# DDR3_SODIMM_SPD_Breakout.net
KiCad netlist of a schematic drawn in Altium Designer
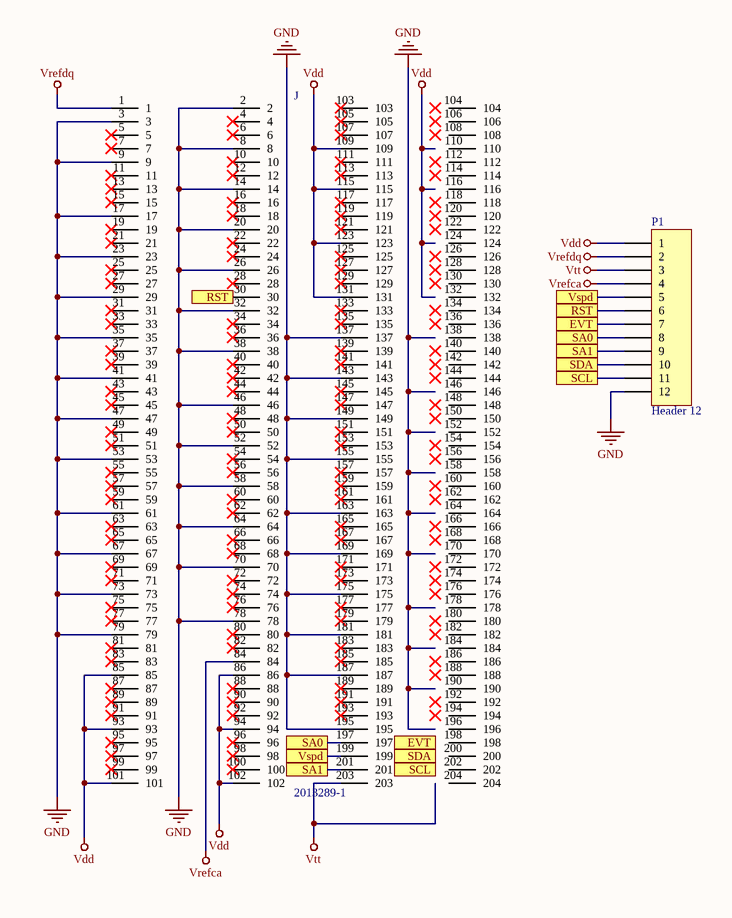
[diagram p0: DDR3 SODIMM SPD Breakout.SchDoc]

(export (version "E")
  (design (tool "Eeschema 10.0.6"))
  (components
    (comp (ref "J")
      (value "2013289-1")
      (footprint "2020-09-26_17-27-19:TE_2013289-1")
      (description "204 Position 0.6 mm Pitch Right Angle Surface Mount Socket DIMM Connector")
      (fields (field (name "DIGI-KEY_PART_NUMBER") "A115021-ND") (field (name "MF") "TE Connectivity"))
      (libsource (lib "2020-09-26_17-27-19") (part "2013289-1"))
    )
    (comp (ref "P1")
      (value "Header 12")
      (footprint "HDR1X12")
      (description "Header, 12-Pin")
      (fields (field (name "PUBLISHER") "Altium Limited"))
      (libsource (lib "Miscellaneous Connectors") (part "Header 12"))
    )
  )
  (nets
    (net (code "1") (name "/EVT") (class "Default")
      (node (ref "P1") (pin "7") (pinfunction "7_7") (pintype "passive"))
    )
    (net (code "2") (name "/RST") (class "Default")
      (node (ref "J") (pin "30") (pinfunction "30_30") (pintype "passive"))
      (node (ref "P1") (pin "6") (pinfunction "6_6") (pintype "passive"))
    )
    (net (code "3") (name "/SA0") (class "Default")
      (node (ref "J") (pin "197") (pinfunction "197_197") (pintype "passive"))
      (node (ref "P1") (pin "8") (pinfunction "8_8") (pintype "passive"))
    )
    (net (code "4") (name "/SA1") (class "Default")
      (node (ref "J") (pin "201") (pinfunction "201_201") (pintype "passive"))
      (node (ref "P1") (pin "9") (pinfunction "9_9") (pintype "passive"))
    )
    (net (code "5") (name "/SCL") (class "Default")
      (node (ref "P1") (pin "11") (pinfunction "11_11") (pintype "passive"))
    )
    (net (code "6") (name "/SDA") (class "Default")
      (node (ref "P1") (pin "10") (pinfunction "10_10") (pintype "passive"))
    )
    (net (code "7") (name "/Vspd") (class "Default")
      (node (ref "J") (pin "199") (pinfunction "199_199") (pintype "passive"))
      (node (ref "P1") (pin "5") (pinfunction "5_5") (pintype "passive"))
    )
    (net (code "8") (name "GND") (class "Default")
      (node (ref "J") (pin "137") (pinfunction "137_137") (pintype "passive"))
      (node (ref "J") (pin "14") (pinfunction "14_14") (pintype "passive"))
      (node (ref "J") (pin "143") (pinfunction "143_143") (pintype "passive"))
      (node (ref "J") (pin "149") (pinfunction "149_149") (pintype "passive"))
      (node (ref "J") (pin "155") (pinfunction "155_155") (pintype "passive"))
      (node (ref "J") (pin "163") (pinfunction "163_163") (pintype "passive"))
      (node (ref "J") (pin "169") (pinfunction "169_169") (pintype "passive"))
      (node (ref "J") (pin "17") (pinfunction "17_17") (pintype "passive"))
      (node (ref "J") (pin "175") (pinfunction "175_175") (pintype "passive"))
      (node (ref "J") (pin "181") (pinfunction "181_181") (pintype "passive"))
      (node (ref "J") (pin "187") (pinfunction "187_187") (pintype "passive"))
      (node (ref "J") (pin "195") (pinfunction "195_195") (pintype "passive"))
      (node (ref "J") (pin "2") (pinfunction "2_2") (pintype "passive"))
      (node (ref "J") (pin "20") (pinfunction "20_20") (pintype "passive"))
      (node (ref "J") (pin "23") (pinfunction "23_23") (pintype "passive"))
      (node (ref "J") (pin "26") (pinfunction "26_26") (pintype "passive"))
      (node (ref "J") (pin "29") (pinfunction "29_29") (pintype "passive"))
      (node (ref "J") (pin "3") (pinfunction "3_3") (pintype "passive"))
      (node (ref "J") (pin "32") (pinfunction "32_32") (pintype "passive"))
      (node (ref "J") (pin "35") (pinfunction "35_35") (pintype "passive"))
      (node (ref "J") (pin "38") (pinfunction "38_38") (pintype "passive"))
      (node (ref "J") (pin "41") (pinfunction "41_41") (pintype "passive"))
      (node (ref "J") (pin "46") (pinfunction "46_46") (pintype "passive"))
      (node (ref "J") (pin "47") (pinfunction "47_47") (pintype "passive"))
      (node (ref "J") (pin "52") (pinfunction "52_52") (pintype "passive"))
      (node (ref "J") (pin "53") (pinfunction "53_53") (pintype "passive"))
      (node (ref "J") (pin "58") (pinfunction "58_58") (pintype "passive"))
      (node (ref "J") (pin "61") (pinfunction "61_61") (pintype "passive"))
      (node (ref "J") (pin "64") (pinfunction "64_64") (pintype "passive"))
      (node (ref "J") (pin "67") (pinfunction "67_67") (pintype "passive"))
      (node (ref "J") (pin "70") (pinfunction "70_70") (pintype "passive"))
      (node (ref "J") (pin "73") (pinfunction "73_73") (pintype "passive"))
      (node (ref "J") (pin "78") (pinfunction "78_78") (pintype "passive"))
      (node (ref "J") (pin "79") (pinfunction "79_79") (pintype "passive"))
      (node (ref "J") (pin "8") (pinfunction "8_8") (pintype "passive"))
      (node (ref "J") (pin "9") (pinfunction "9_9") (pintype "passive"))
      (node (ref "P1") (pin "12") (pinfunction "12_12") (pintype "passive"))
    )
    (net (code "9") (name "Vdd") (class "Default")
      (node (ref "J") (pin "101") (pinfunction "101_101") (pintype "passive"))
      (node (ref "J") (pin "102") (pinfunction "102_102") (pintype "passive"))
      (node (ref "J") (pin "109") (pinfunction "109_109") (pintype "passive"))
      (node (ref "J") (pin "115") (pinfunction "115_115") (pintype "passive"))
      (node (ref "J") (pin "123") (pinfunction "123_123") (pintype "passive"))
      (node (ref "J") (pin "131") (pinfunction "131_131") (pintype "passive"))
      (node (ref "J") (pin "85") (pinfunction "85_85") (pintype "passive"))
      (node (ref "J") (pin "86") (pinfunction "86_86") (pintype "passive"))
      (node (ref "J") (pin "93") (pinfunction "93_93") (pintype "passive"))
      (node (ref "J") (pin "94") (pinfunction "94_94") (pintype "passive"))
      (node (ref "P1") (pin "1") (pinfunction "1_1") (pintype "passive"))
    )
    (net (code "10") (name "Vrefca") (class "Default")
      (node (ref "J") (pin "84") (pinfunction "84_84") (pintype "passive"))
      (node (ref "P1") (pin "4") (pinfunction "4_4") (pintype "passive"))
    )
    (net (code "11") (name "Vrefdq") (class "Default")
      (node (ref "J") (pin "1") (pinfunction "1_1") (pintype "passive"))
      (node (ref "P1") (pin "2") (pinfunction "2_2") (pintype "passive"))
    )
    (net (code "12") (name "Vtt") (class "Default")
      (node (ref "J") (pin "203") (pinfunction "203_203") (pintype "passive"))
      (node (ref "P1") (pin "3") (pinfunction "3_3") (pintype "passive"))
    )
    (net (code "13") (name "unconnected-(J-Pad4)") (class "Default")
      (node (ref "J") (pin "4") (pinfunction "4_4") (pintype "passive+no_connect"))
    )
    (net (code "14") (name "unconnected-(J-Pad5)") (class "Default")
      (node (ref "J") (pin "5") (pinfunction "5_5") (pintype "passive+no_connect"))
    )
    (net (code "15") (name "unconnected-(J-Pad6)") (class "Default")
      (node (ref "J") (pin "6") (pinfunction "6_6") (pintype "passive+no_connect"))
    )
    (net (code "16") (name "unconnected-(J-Pad7)") (class "Default")
      (node (ref "J") (pin "7") (pinfunction "7_7") (pintype "passive+no_connect"))
    )
    (net (code "17") (name "unconnected-(J-Pad10)") (class "Default")
      (node (ref "J") (pin "10") (pinfunction "10_10") (pintype "passive+no_connect"))
    )
    (net (code "18") (name "unconnected-(J-Pad11)") (class "Default")
      (node (ref "J") (pin "11") (pinfunction "11_11") (pintype "passive+no_connect"))
    )
    (net (code "19") (name "unconnected-(J-Pad12)") (class "Default")
      (node (ref "J") (pin "12") (pinfunction "12_12") (pintype "passive+no_connect"))
    )
    (net (code "20") (name "unconnected-(J-Pad13)") (class "Default")
      (node (ref "J") (pin "13") (pinfunction "13_13") (pintype "passive+no_connect"))
    )
    (net (code "21") (name "unconnected-(J-Pad15)") (class "Default")
      (node (ref "J") (pin "15") (pinfunction "15_15") (pintype "passive+no_connect"))
    )
    (net (code "22") (name "unconnected-(J-Pad16)") (class "Default")
      (node (ref "J") (pin "16") (pinfunction "16_16") (pintype "passive+no_connect"))
    )
    (net (code "23") (name "unconnected-(J-Pad18)") (class "Default")
      (node (ref "J") (pin "18") (pinfunction "18_18") (pintype "passive+no_connect"))
    )
    (net (code "24") (name "unconnected-(J-Pad19)") (class "Default")
      (node (ref "J") (pin "19") (pinfunction "19_19") (pintype "passive+no_connect"))
    )
    (net (code "25") (name "unconnected-(J-Pad21)") (class "Default")
      (node (ref "J") (pin "21") (pinfunction "21_21") (pintype "passive+no_connect"))
    )
    (net (code "26") (name "unconnected-(J-Pad22)") (class "Default")
      (node (ref "J") (pin "22") (pinfunction "22_22") (pintype "passive+no_connect"))
    )
    (net (code "27") (name "unconnected-(J-Pad24)") (class "Default")
      (node (ref "J") (pin "24") (pinfunction "24_24") (pintype "passive+no_connect"))
    )
    (net (code "28") (name "unconnected-(J-Pad25)") (class "Default")
      (node (ref "J") (pin "25") (pinfunction "25_25") (pintype "passive+no_connect"))
    )
    (net (code "29") (name "unconnected-(J-Pad27)") (class "Default")
      (node (ref "J") (pin "27") (pinfunction "27_27") (pintype "passive+no_connect"))
    )
    (net (code "30") (name "unconnected-(J-Pad28)") (class "Default")
      (node (ref "J") (pin "28") (pinfunction "28_28") (pintype "passive+no_connect"))
    )
    (net (code "31") (name "unconnected-(J-Pad31)") (class "Default")
      (node (ref "J") (pin "31") (pinfunction "31_31") (pintype "passive+no_connect"))
    )
    (net (code "32") (name "unconnected-(J-Pad33)") (class "Default")
      (node (ref "J") (pin "33") (pinfunction "33_33") (pintype "passive+no_connect"))
    )
    (net (code "33") (name "unconnected-(J-Pad34)") (class "Default")
      (node (ref "J") (pin "34") (pinfunction "34_34") (pintype "passive+no_connect"))
    )
    (net (code "34") (name "unconnected-(J-Pad36)") (class "Default")
      (node (ref "J") (pin "36") (pinfunction "36_36") (pintype "passive+no_connect"))
    )
    (net (code "35") (name "unconnected-(J-Pad37)") (class "Default")
      (node (ref "J") (pin "37") (pinfunction "37_37") (pintype "passive+no_connect"))
    )
    (net (code "36") (name "unconnected-(J-Pad39)") (class "Default")
      (node (ref "J") (pin "39") (pinfunction "39_39") (pintype "passive+no_connect"))
    )
    (net (code "37") (name "unconnected-(J-Pad40)") (class "Default")
      (node (ref "J") (pin "40") (pinfunction "40_40") (pintype "passive+no_connect"))
    )
    (net (code "38") (name "unconnected-(J-Pad42)") (class "Default")
      (node (ref "J") (pin "42") (pinfunction "42_42") (pintype "passive+no_connect"))
    )
    (net (code "39") (name "unconnected-(J-Pad43)") (class "Default")
      (node (ref "J") (pin "43") (pinfunction "43_43") (pintype "passive+no_connect"))
    )
    (net (code "40") (name "unconnected-(J-Pad44)") (class "Default")
      (node (ref "J") (pin "44") (pinfunction "44_44") (pintype "passive+no_connect"))
    )
    (net (code "41") (name "unconnected-(J-Pad45)") (class "Default")
      (node (ref "J") (pin "45") (pinfunction "45_45") (pintype "passive+no_connect"))
    )
    (net (code "42") (name "unconnected-(J-Pad48)") (class "Default")
      (node (ref "J") (pin "48") (pinfunction "48_48") (pintype "passive+no_connect"))
    )
    (net (code "43") (name "unconnected-(J-Pad49)") (class "Default")
      (node (ref "J") (pin "49") (pinfunction "49_49") (pintype "passive+no_connect"))
    )
    (net (code "44") (name "unconnected-(J-Pad50)") (class "Default")
      (node (ref "J") (pin "50") (pinfunction "50_50") (pintype "passive+no_connect"))
    )
    (net (code "45") (name "unconnected-(J-Pad51)") (class "Default")
      (node (ref "J") (pin "51") (pinfunction "51_51") (pintype "passive+no_connect"))
    )
    (net (code "46") (name "unconnected-(J-Pad54)") (class "Default")
      (node (ref "J") (pin "54") (pinfunction "54_54") (pintype "passive+no_connect"))
    )
    (net (code "47") (name "unconnected-(J-Pad55)") (class "Default")
      (node (ref "J") (pin "55") (pinfunction "55_55") (pintype "passive+no_connect"))
    )
    (net (code "48") (name "unconnected-(J-Pad56)") (class "Default")
      (node (ref "J") (pin "56") (pinfunction "56_56") (pintype "passive+no_connect"))
    )
    (net (code "49") (name "unconnected-(J-Pad57)") (class "Default")
      (node (ref "J") (pin "57") (pinfunction "57_57") (pintype "passive+no_connect"))
    )
    (net (code "50") (name "unconnected-(J-Pad59)") (class "Default")
      (node (ref "J") (pin "59") (pinfunction "59_59") (pintype "passive+no_connect"))
    )
    (net (code "51") (name "unconnected-(J-Pad60)") (class "Default")
      (node (ref "J") (pin "60") (pinfunction "60_60") (pintype "passive+no_connect"))
    )
    (net (code "52") (name "unconnected-(J-Pad62)") (class "Default")
      (node (ref "J") (pin "62") (pinfunction "62_62") (pintype "passive+no_connect"))
    )
    (net (code "53") (name "unconnected-(J-Pad63)") (class "Default")
      (node (ref "J") (pin "63") (pinfunction "63_63") (pintype "passive+no_connect"))
    )
    (net (code "54") (name "unconnected-(J-Pad65)") (class "Default")
      (node (ref "J") (pin "65") (pinfunction "65_65") (pintype "passive+no_connect"))
    )
    (net (code "55") (name "unconnected-(J-Pad66)") (class "Default")
      (node (ref "J") (pin "66") (pinfunction "66_66") (pintype "passive+no_connect"))
    )
    (net (code "56") (name "unconnected-(J-Pad68)") (class "Default")
      (node (ref "J") (pin "68") (pinfunction "68_68") (pintype "passive+no_connect"))
    )
    (net (code "57") (name "unconnected-(J-Pad69)") (class "Default")
      (node (ref "J") (pin "69") (pinfunction "69_69") (pintype "passive+no_connect"))
    )
    (net (code "58") (name "unconnected-(J-Pad71)") (class "Default")
      (node (ref "J") (pin "71") (pinfunction "71_71") (pintype "passive+no_connect"))
    )
    (net (code "59") (name "unconnected-(J-Pad72)") (class "Default")
      (node (ref "J") (pin "72") (pinfunction "72_72") (pintype "passive+no_connect"))
    )
    (net (code "60") (name "unconnected-(J-Pad74)") (class "Default")
      (node (ref "J") (pin "74") (pinfunction "74_74") (pintype "passive+no_connect"))
    )
    (net (code "61") (name "unconnected-(J-Pad75)") (class "Default")
      (node (ref "J") (pin "75") (pinfunction "75_75") (pintype "passive+no_connect"))
    )
    (net (code "62") (name "unconnected-(J-Pad76)") (class "Default")
      (node (ref "J") (pin "76") (pinfunction "76_76") (pintype "passive+no_connect"))
    )
    (net (code "63") (name "unconnected-(J-Pad77)") (class "Default")
      (node (ref "J") (pin "77") (pinfunction "77_77") (pintype "passive+no_connect"))
    )
    (net (code "64") (name "unconnected-(J-Pad80)") (class "Default")
      (node (ref "J") (pin "80") (pinfunction "80_80") (pintype "passive+no_connect"))
    )
    (net (code "65") (name "unconnected-(J-Pad81)") (class "Default")
      (node (ref "J") (pin "81") (pinfunction "81_81") (pintype "passive+no_connect"))
    )
    (net (code "66") (name "unconnected-(J-Pad82)") (class "Default")
      (node (ref "J") (pin "82") (pinfunction "82_82") (pintype "passive+no_connect"))
    )
    (net (code "67") (name "unconnected-(J-Pad83)") (class "Default")
      (node (ref "J") (pin "83") (pinfunction "83_83") (pintype "passive+no_connect"))
    )
    (net (code "68") (name "unconnected-(J-Pad87)") (class "Default")
      (node (ref "J") (pin "87") (pinfunction "87_87") (pintype "passive+no_connect"))
    )
    (net (code "69") (name "unconnected-(J-Pad88)") (class "Default")
      (node (ref "J") (pin "88") (pinfunction "88_88") (pintype "passive+no_connect"))
    )
    (net (code "70") (name "unconnected-(J-Pad89)") (class "Default")
      (node (ref "J") (pin "89") (pinfunction "89_89") (pintype "passive+no_connect"))
    )
    (net (code "71") (name "unconnected-(J-Pad90)") (class "Default")
      (node (ref "J") (pin "90") (pinfunction "90_90") (pintype "passive+no_connect"))
    )
    (net (code "72") (name "unconnected-(J-Pad91)") (class "Default")
      (node (ref "J") (pin "91") (pinfunction "91_91") (pintype "passive+no_connect"))
    )
    (net (code "73") (name "unconnected-(J-Pad92)") (class "Default")
      (node (ref "J") (pin "92") (pinfunction "92_92") (pintype "passive+no_connect"))
    )
    (net (code "74") (name "unconnected-(J-Pad95)") (class "Default")
      (node (ref "J") (pin "95") (pinfunction "95_95") (pintype "passive+no_connect"))
    )
    (net (code "75") (name "unconnected-(J-Pad96)") (class "Default")
      (node (ref "J") (pin "96") (pinfunction "96_96") (pintype "passive+no_connect"))
    )
    (net (code "76") (name "unconnected-(J-Pad97)") (class "Default")
      (node (ref "J") (pin "97") (pinfunction "97_97") (pintype "passive+no_connect"))
    )
    (net (code "77") (name "unconnected-(J-Pad98)") (class "Default")
      (node (ref "J") (pin "98") (pinfunction "98_98") (pintype "passive+no_connect"))
    )
    (net (code "78") (name "unconnected-(J-Pad99)") (class "Default")
      (node (ref "J") (pin "99") (pinfunction "99_99") (pintype "passive+no_connect"))
    )
    (net (code "79") (name "unconnected-(J-Pad100)") (class "Default")
      (node (ref "J") (pin "100") (pinfunction "100_100") (pintype "passive+no_connect"))
    )
    (net (code "80") (name "unconnected-(J-Pad103)") (class "Default")
      (node (ref "J") (pin "103") (pinfunction "103_103") (pintype "passive+no_connect"))
    )
    (net (code "81") (name "unconnected-(J-Pad104)") (class "Default")
      (node (ref "J") (pin "104") (pinfunction "104_104") (pintype "passive"))
    )
    (net (code "82") (name "unconnected-(J-Pad105)") (class "Default")
      (node (ref "J") (pin "105") (pinfunction "105_105") (pintype "passive+no_connect"))
    )
    (net (code "83") (name "unconnected-(J-Pad106)") (class "Default")
      (node (ref "J") (pin "106") (pinfunction "106_106") (pintype "passive"))
    )
    (net (code "84") (name "unconnected-(J-Pad107)") (class "Default")
      (node (ref "J") (pin "107") (pinfunction "107_107") (pintype "passive+no_connect"))
    )
    (net (code "85") (name "unconnected-(J-Pad108)") (class "Default")
      (node (ref "J") (pin "108") (pinfunction "108_108") (pintype "passive"))
    )
    (net (code "86") (name "unconnected-(J-Pad110)") (class "Default")
      (node (ref "J") (pin "110") (pinfunction "110_110") (pintype "passive"))
    )
    (net (code "87") (name "unconnected-(J-Pad111)") (class "Default")
      (node (ref "J") (pin "111") (pinfunction "111_111") (pintype "passive+no_connect"))
    )
    (net (code "88") (name "unconnected-(J-Pad112)") (class "Default")
      (node (ref "J") (pin "112") (pinfunction "112_112") (pintype "passive"))
    )
    (net (code "89") (name "unconnected-(J-Pad113)") (class "Default")
      (node (ref "J") (pin "113") (pinfunction "113_113") (pintype "passive+no_connect"))
    )
    (net (code "90") (name "unconnected-(J-Pad114)") (class "Default")
      (node (ref "J") (pin "114") (pinfunction "114_114") (pintype "passive"))
    )
    (net (code "91") (name "unconnected-(J-Pad116)") (class "Default")
      (node (ref "J") (pin "116") (pinfunction "116_116") (pintype "passive"))
    )
    (net (code "92") (name "unconnected-(J-Pad117)") (class "Default")
      (node (ref "J") (pin "117") (pinfunction "117_117") (pintype "passive+no_connect"))
    )
    (net (code "93") (name "unconnected-(J-Pad118)") (class "Default")
      (node (ref "J") (pin "118") (pinfunction "118_118") (pintype "passive"))
    )
    (net (code "94") (name "unconnected-(J-Pad119)") (class "Default")
      (node (ref "J") (pin "119") (pinfunction "119_119") (pintype "passive+no_connect"))
    )
    (net (code "95") (name "unconnected-(J-Pad120)") (class "Default")
      (node (ref "J") (pin "120") (pinfunction "120_120") (pintype "passive"))
    )
    (net (code "96") (name "unconnected-(J-Pad121)") (class "Default")
      (node (ref "J") (pin "121") (pinfunction "121_121") (pintype "passive+no_connect"))
    )
    (net (code "97") (name "unconnected-(J-Pad122)") (class "Default")
      (node (ref "J") (pin "122") (pinfunction "122_122") (pintype "passive"))
    )
    (net (code "98") (name "unconnected-(J-Pad124)") (class "Default")
      (node (ref "J") (pin "124") (pinfunction "124_124") (pintype "passive"))
    )
    (net (code "99") (name "unconnected-(J-Pad125)") (class "Default")
      (node (ref "J") (pin "125") (pinfunction "125_125") (pintype "passive+no_connect"))
    )
    (net (code "100") (name "unconnected-(J-Pad126)") (class "Default")
      (node (ref "J") (pin "126") (pinfunction "126_126") (pintype "passive"))
    )
    (net (code "101") (name "unconnected-(J-Pad127)") (class "Default")
      (node (ref "J") (pin "127") (pinfunction "127_127") (pintype "passive+no_connect"))
    )
    (net (code "102") (name "unconnected-(J-Pad128)") (class "Default")
      (node (ref "J") (pin "128") (pinfunction "128_128") (pintype "passive"))
    )
    (net (code "103") (name "unconnected-(J-Pad129)") (class "Default")
      (node (ref "J") (pin "129") (pinfunction "129_129") (pintype "passive+no_connect"))
    )
    (net (code "104") (name "unconnected-(J-Pad130)") (class "Default")
      (node (ref "J") (pin "130") (pinfunction "130_130") (pintype "passive"))
    )
    (net (code "105") (name "unconnected-(J-Pad132)") (class "Default")
      (node (ref "J") (pin "132") (pinfunction "132_132") (pintype "passive"))
    )
    (net (code "106") (name "unconnected-(J-Pad133)") (class "Default")
      (node (ref "J") (pin "133") (pinfunction "133_133") (pintype "passive+no_connect"))
    )
    (net (code "107") (name "unconnected-(J-Pad134)") (class "Default")
      (node (ref "J") (pin "134") (pinfunction "134_134") (pintype "passive"))
    )
    (net (code "108") (name "unconnected-(J-Pad135)") (class "Default")
      (node (ref "J") (pin "135") (pinfunction "135_135") (pintype "passive+no_connect"))
    )
    (net (code "109") (name "unconnected-(J-Pad136)") (class "Default")
      (node (ref "J") (pin "136") (pinfunction "136_136") (pintype "passive"))
    )
    (net (code "110") (name "unconnected-(J-Pad138)") (class "Default")
      (node (ref "J") (pin "138") (pinfunction "138_138") (pintype "passive"))
    )
    (net (code "111") (name "unconnected-(J-Pad139)") (class "Default")
      (node (ref "J") (pin "139") (pinfunction "139_139") (pintype "passive+no_connect"))
    )
    (net (code "112") (name "unconnected-(J-Pad140)") (class "Default")
      (node (ref "J") (pin "140") (pinfunction "140_140") (pintype "passive"))
    )
    (net (code "113") (name "unconnected-(J-Pad141)") (class "Default")
      (node (ref "J") (pin "141") (pinfunction "141_141") (pintype "passive+no_connect"))
    )
    (net (code "114") (name "unconnected-(J-Pad142)") (class "Default")
      (node (ref "J") (pin "142") (pinfunction "142_142") (pintype "passive"))
    )
    (net (code "115") (name "unconnected-(J-Pad144)") (class "Default")
      (node (ref "J") (pin "144") (pinfunction "144_144") (pintype "passive"))
    )
    (net (code "116") (name "unconnected-(J-Pad145)") (class "Default")
      (node (ref "J") (pin "145") (pinfunction "145_145") (pintype "passive+no_connect"))
    )
    (net (code "117") (name "unconnected-(J-Pad146)") (class "Default")
      (node (ref "J") (pin "146") (pinfunction "146_146") (pintype "passive"))
    )
    (net (code "118") (name "unconnected-(J-Pad147)") (class "Default")
      (node (ref "J") (pin "147") (pinfunction "147_147") (pintype "passive+no_connect"))
    )
    (net (code "119") (name "unconnected-(J-Pad148)") (class "Default")
      (node (ref "J") (pin "148") (pinfunction "148_148") (pintype "passive"))
    )
    (net (code "120") (name "unconnected-(J-Pad150)") (class "Default")
      (node (ref "J") (pin "150") (pinfunction "150_150") (pintype "passive"))
    )
    (net (code "121") (name "unconnected-(J-Pad151)") (class "Default")
      (node (ref "J") (pin "151") (pinfunction "151_151") (pintype "passive+no_connect"))
    )
    (net (code "122") (name "unconnected-(J-Pad152)") (class "Default")
      (node (ref "J") (pin "152") (pinfunction "152_152") (pintype "passive"))
    )
    (net (code "123") (name "unconnected-(J-Pad153)") (class "Default")
      (node (ref "J") (pin "153") (pinfunction "153_153") (pintype "passive+no_connect"))
    )
    (net (code "124") (name "unconnected-(J-Pad154)") (class "Default")
      (node (ref "J") (pin "154") (pinfunction "154_154") (pintype "passive"))
    )
    (net (code "125") (name "unconnected-(J-Pad156)") (class "Default")
      (node (ref "J") (pin "156") (pinfunction "156_156") (pintype "passive"))
    )
    (net (code "126") (name "unconnected-(J-Pad157)") (class "Default")
      (node (ref "J") (pin "157") (pinfunction "157_157") (pintype "passive+no_connect"))
    )
    (net (code "127") (name "unconnected-(J-Pad158)") (class "Default")
      (node (ref "J") (pin "158") (pinfunction "158_158") (pintype "passive"))
    )
    (net (code "128") (name "unconnected-(J-Pad159)") (class "Default")
      (node (ref "J") (pin "159") (pinfunction "159_159") (pintype "passive+no_connect"))
    )
    (net (code "129") (name "unconnected-(J-Pad160)") (class "Default")
      (node (ref "J") (pin "160") (pinfunction "160_160") (pintype "passive"))
    )
    (net (code "130") (name "unconnected-(J-Pad161)") (class "Default")
      (node (ref "J") (pin "161") (pinfunction "161_161") (pintype "passive+no_connect"))
    )
    (net (code "131") (name "unconnected-(J-Pad162)") (class "Default")
      (node (ref "J") (pin "162") (pinfunction "162_162") (pintype "passive"))
    )
    (net (code "132") (name "unconnected-(J-Pad164)") (class "Default")
      (node (ref "J") (pin "164") (pinfunction "164_164") (pintype "passive"))
    )
    (net (code "133") (name "unconnected-(J-Pad165)") (class "Default")
      (node (ref "J") (pin "165") (pinfunction "165_165") (pintype "passive+no_connect"))
    )
    (net (code "134") (name "unconnected-(J-Pad166)") (class "Default")
      (node (ref "J") (pin "166") (pinfunction "166_166") (pintype "passive"))
    )
    (net (code "135") (name "unconnected-(J-Pad167)") (class "Default")
      (node (ref "J") (pin "167") (pinfunction "167_167") (pintype "passive+no_connect"))
    )
    (net (code "136") (name "unconnected-(J-Pad168)") (class "Default")
      (node (ref "J") (pin "168") (pinfunction "168_168") (pintype "passive"))
    )
    (net (code "137") (name "unconnected-(J-Pad170)") (class "Default")
      (node (ref "J") (pin "170") (pinfunction "170_170") (pintype "passive"))
    )
    (net (code "138") (name "unconnected-(J-Pad171)") (class "Default")
      (node (ref "J") (pin "171") (pinfunction "171_171") (pintype "passive+no_connect"))
    )
    (net (code "139") (name "unconnected-(J-Pad172)") (class "Default")
      (node (ref "J") (pin "172") (pinfunction "172_172") (pintype "passive"))
    )
    (net (code "140") (name "unconnected-(J-Pad173)") (class "Default")
      (node (ref "J") (pin "173") (pinfunction "173_173") (pintype "passive+no_connect"))
    )
    (net (code "141") (name "unconnected-(J-Pad174)") (class "Default")
      (node (ref "J") (pin "174") (pinfunction "174_174") (pintype "passive"))
    )
    (net (code "142") (name "unconnected-(J-Pad176)") (class "Default")
      (node (ref "J") (pin "176") (pinfunction "176_176") (pintype "passive"))
    )
    (net (code "143") (name "unconnected-(J-Pad177)") (class "Default")
      (node (ref "J") (pin "177") (pinfunction "177_177") (pintype "passive+no_connect"))
    )
    (net (code "144") (name "unconnected-(J-Pad178)") (class "Default")
      (node (ref "J") (pin "178") (pinfunction "178_178") (pintype "passive"))
    )
    (net (code "145") (name "unconnected-(J-Pad179)") (class "Default")
      (node (ref "J") (pin "179") (pinfunction "179_179") (pintype "passive+no_connect"))
    )
    (net (code "146") (name "unconnected-(J-Pad180)") (class "Default")
      (node (ref "J") (pin "180") (pinfunction "180_180") (pintype "passive"))
    )
    (net (code "147") (name "unconnected-(J-Pad182)") (class "Default")
      (node (ref "J") (pin "182") (pinfunction "182_182") (pintype "passive"))
    )
    (net (code "148") (name "unconnected-(J-Pad183)") (class "Default")
      (node (ref "J") (pin "183") (pinfunction "183_183") (pintype "passive+no_connect"))
    )
    (net (code "149") (name "unconnected-(J-Pad184)") (class "Default")
      (node (ref "J") (pin "184") (pinfunction "184_184") (pintype "passive"))
    )
    (net (code "150") (name "unconnected-(J-Pad185)") (class "Default")
      (node (ref "J") (pin "185") (pinfunction "185_185") (pintype "passive+no_connect"))
    )
    (net (code "151") (name "unconnected-(J-Pad186)") (class "Default")
      (node (ref "J") (pin "186") (pinfunction "186_186") (pintype "passive"))
    )
    (net (code "152") (name "unconnected-(J-Pad188)") (class "Default")
      (node (ref "J") (pin "188") (pinfunction "188_188") (pintype "passive"))
    )
    (net (code "153") (name "unconnected-(J-Pad189)") (class "Default")
      (node (ref "J") (pin "189") (pinfunction "189_189") (pintype "passive+no_connect"))
    )
    (net (code "154") (name "unconnected-(J-Pad190)") (class "Default")
      (node (ref "J") (pin "190") (pinfunction "190_190") (pintype "passive"))
    )
    (net (code "155") (name "unconnected-(J-Pad191)") (class "Default")
      (node (ref "J") (pin "191") (pinfunction "191_191") (pintype "passive+no_connect"))
    )
    (net (code "156") (name "unconnected-(J-Pad192)") (class "Default")
      (node (ref "J") (pin "192") (pinfunction "192_192") (pintype "passive"))
    )
    (net (code "157") (name "unconnected-(J-Pad193)") (class "Default")
      (node (ref "J") (pin "193") (pinfunction "193_193") (pintype "passive+no_connect"))
    )
    (net (code "158") (name "unconnected-(J-Pad194)") (class "Default")
      (node (ref "J") (pin "194") (pinfunction "194_194") (pintype "passive"))
    )
    (net (code "159") (name "unconnected-(J-Pad196)") (class "Default")
      (node (ref "J") (pin "196") (pinfunction "196_196") (pintype "passive"))
    )
    (net (code "160") (name "unconnected-(J-Pad198)") (class "Default")
      (node (ref "J") (pin "198") (pinfunction "198_198") (pintype "passive"))
    )
    (net (code "161") (name "unconnected-(J-Pad200)") (class "Default")
      (node (ref "J") (pin "200") (pinfunction "200_200") (pintype "passive"))
    )
    (net (code "162") (name "unconnected-(J-Pad202)") (class "Default")
      (node (ref "J") (pin "202") (pinfunction "202_202") (pintype "passive"))
    )
    (net (code "163") (name "unconnected-(J-Pad204)") (class "Default")
      (node (ref "J") (pin "204") (pinfunction "204_204") (pintype "passive"))
    )
  )
)
